# Sheet1.net
KiCad netlist of a schematic drawn in Altium Designer
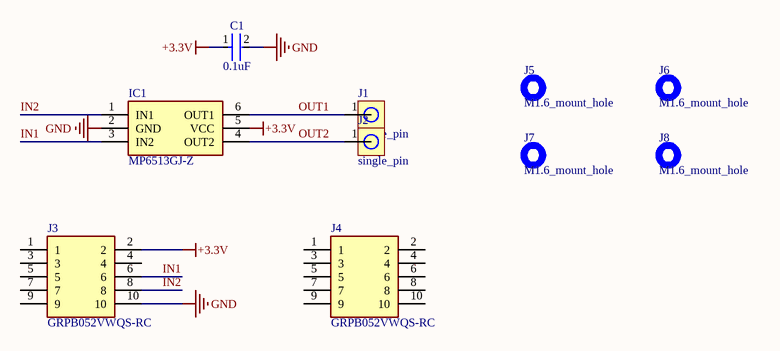
[diagram p0: Sheet1.SchDoc]

(export (version "E")
  (design (tool "Eeschema 10.0.6"))
  (components
    (comp (ref "C1")
      (value "0.1uF")
      (footprint "FP-GCM188-0_1-IPC_B")
      (description "Ceramic Capacitor for Automotive 100nF  ±10% 50VDC X8L 0603 Paper T/R")
      (fields (field (name "TOLERANCE") "10%") (field (name "VOLTAGE") "50V"))
      (libsource (lib "Altium Content Vault") (part "02cd4be3c70576c341d710602a673aa"))
    )
    (comp (ref "IC1")
      (value "MP6513GJ-Z")
      (footprint "SamacSys:SOT95P280X100-6N")
      (description "Integrated Circuit")
      (fields (field (name "MOUSER PART NUMBER") "946-MP6513GJ-Z"))
      (libsource (lib "*") (part "MP6513GJ-Z"))
    )
    (comp (ref "J1")
      (value "single_pin")
      (footprint "1mm_single_pin_thr")
      (description "single pin header")
      (libsource (lib "Schlib1") (part "single_pin"))
    )
    (comp (ref "J2")
      (value "single_pin")
      (footprint "1mm_single_pin_thr")
      (description "single pin header")
      (libsource (lib "Schlib1") (part "single_pin"))
    )
    (comp (ref "J3")
      (value "GRPB052VWQS-RC")
      (footprint "SamacSys:HUSSP10W40P127_2X5_635X340X400P")
      (description "Connector")
      (libsource (lib "*") (part "GRPB052VWQS-RC"))
    )
    (comp (ref "J4")
      (value "GRPB052VWQS-RC")
      (footprint "SamacSys:HUSSP10W40P127_2X5_635X340X400P")
      (description "Connector")
      (libsource (lib "*") (part "GRPB052VWQS-RC"))
    )
    (comp (ref "J5")
      (value "M1.6_mount_hole")
      (footprint "M1.6_mount_hole")
      (libsource (lib "Schlib1") (part "M1.6_mount_hole"))
    )
    (comp (ref "J6")
      (value "M1.6_mount_hole")
      (footprint "M1.6_mount_hole")
      (libsource (lib "Schlib1") (part "M1.6_mount_hole"))
    )
    (comp (ref "J7")
      (value "M1.6_mount_hole")
      (footprint "M1.6_mount_hole")
      (libsource (lib "Schlib1") (part "M1.6_mount_hole"))
    )
    (comp (ref "J8")
      (value "M1.6_mount_hole")
      (footprint "M1.6_mount_hole")
      (libsource (lib "Schlib1") (part "M1.6_mount_hole"))
    )
  )
  (nets
    (net (code "1") (name "+3.3V") (class "Default")
      (node (ref "C1") (pin "1") (pinfunction "1_1") (pintype "passive"))
      (node (ref "IC1") (pin "5") (pinfunction "VCC_5") (pintype "passive"))
      (node (ref "J3") (pin "2") (pinfunction "2_2") (pintype "passive"))
    )
    (net (code "2") (name "/IN1") (class "Default")
      (node (ref "IC1") (pin "3") (pinfunction "IN2_3") (pintype "passive"))
      (node (ref "J3") (pin "6") (pinfunction "6_6") (pintype "passive"))
    )
    (net (code "3") (name "/IN2") (class "Default")
      (node (ref "IC1") (pin "1") (pinfunction "IN1_1") (pintype "passive"))
      (node (ref "J3") (pin "8") (pinfunction "8_8") (pintype "passive"))
    )
    (net (code "4") (name "/OUT1") (class "Default")
      (node (ref "IC1") (pin "6") (pinfunction "OUT1_6") (pintype "passive"))
      (node (ref "J1") (pin "1") (pinfunction "1_1") (pintype "passive"))
    )
    (net (code "5") (name "/OUT2") (class "Default")
      (node (ref "IC1") (pin "4") (pinfunction "OUT2_4") (pintype "passive"))
      (node (ref "J2") (pin "1") (pinfunction "1_1") (pintype "passive"))
    )
    (net (code "6") (name "GND") (class "Default")
      (node (ref "C1") (pin "2") (pinfunction "2_2") (pintype "passive"))
      (node (ref "IC1") (pin "2") (pinfunction "GND_2") (pintype "passive"))
      (node (ref "J3") (pin "10") (pinfunction "10_10") (pintype "passive"))
    )
    (net (code "7") (name "unconnected-(J3-Pad1)") (class "Default")
      (node (ref "J3") (pin "1") (pinfunction "1_1") (pintype "passive"))
    )
    (net (code "8") (name "unconnected-(J3-Pad3)") (class "Default")
      (node (ref "J3") (pin "3") (pinfunction "3_3") (pintype "passive"))
    )
    (net (code "9") (name "unconnected-(J3-Pad4)") (class "Default")
      (node (ref "J3") (pin "4") (pinfunction "4_4") (pintype "passive"))
    )
    (net (code "10") (name "unconnected-(J3-Pad5)") (class "Default")
      (node (ref "J3") (pin "5") (pinfunction "5_5") (pintype "passive"))
    )
    (net (code "11") (name "unconnected-(J3-Pad7)") (class "Default")
      (node (ref "J3") (pin "7") (pinfunction "7_7") (pintype "passive"))
    )
    (net (code "12") (name "unconnected-(J3-Pad9)") (class "Default")
      (node (ref "J3") (pin "9") (pinfunction "9_9") (pintype "passive"))
    )
    (net (code "13") (name "unconnected-(J4-Pad1)") (class "Default")
      (node (ref "J4") (pin "1") (pinfunction "1_1") (pintype "passive"))
    )
    (net (code "14") (name "unconnected-(J4-Pad2)") (class "Default")
      (node (ref "J4") (pin "2") (pinfunction "2_2") (pintype "passive"))
    )
    (net (code "15") (name "unconnected-(J4-Pad3)") (class "Default")
      (node (ref "J4") (pin "3") (pinfunction "3_3") (pintype "passive"))
    )
    (net (code "16") (name "unconnected-(J4-Pad4)") (class "Default")
      (node (ref "J4") (pin "4") (pinfunction "4_4") (pintype "passive"))
    )
    (net (code "17") (name "unconnected-(J4-Pad5)") (class "Default")
      (node (ref "J4") (pin "5") (pinfunction "5_5") (pintype "passive"))
    )
    (net (code "18") (name "unconnected-(J4-Pad6)") (class "Default")
      (node (ref "J4") (pin "6") (pinfunction "6_6") (pintype "passive"))
    )
    (net (code "19") (name "unconnected-(J4-Pad7)") (class "Default")
      (node (ref "J4") (pin "7") (pinfunction "7_7") (pintype "passive"))
    )
    (net (code "20") (name "unconnected-(J4-Pad8)") (class "Default")
      (node (ref "J4") (pin "8") (pinfunction "8_8") (pintype "passive"))
    )
    (net (code "21") (name "unconnected-(J4-Pad9)") (class "Default")
      (node (ref "J4") (pin "9") (pinfunction "9_9") (pintype "passive"))
    )
    (net (code "22") (name "unconnected-(J4-Pad10)") (class "Default")
      (node (ref "J4") (pin "10") (pinfunction "10_10") (pintype "passive"))
    )
  )
)
